# wall_power.net
KiCad netlist of a schematic drawn in EAGLE
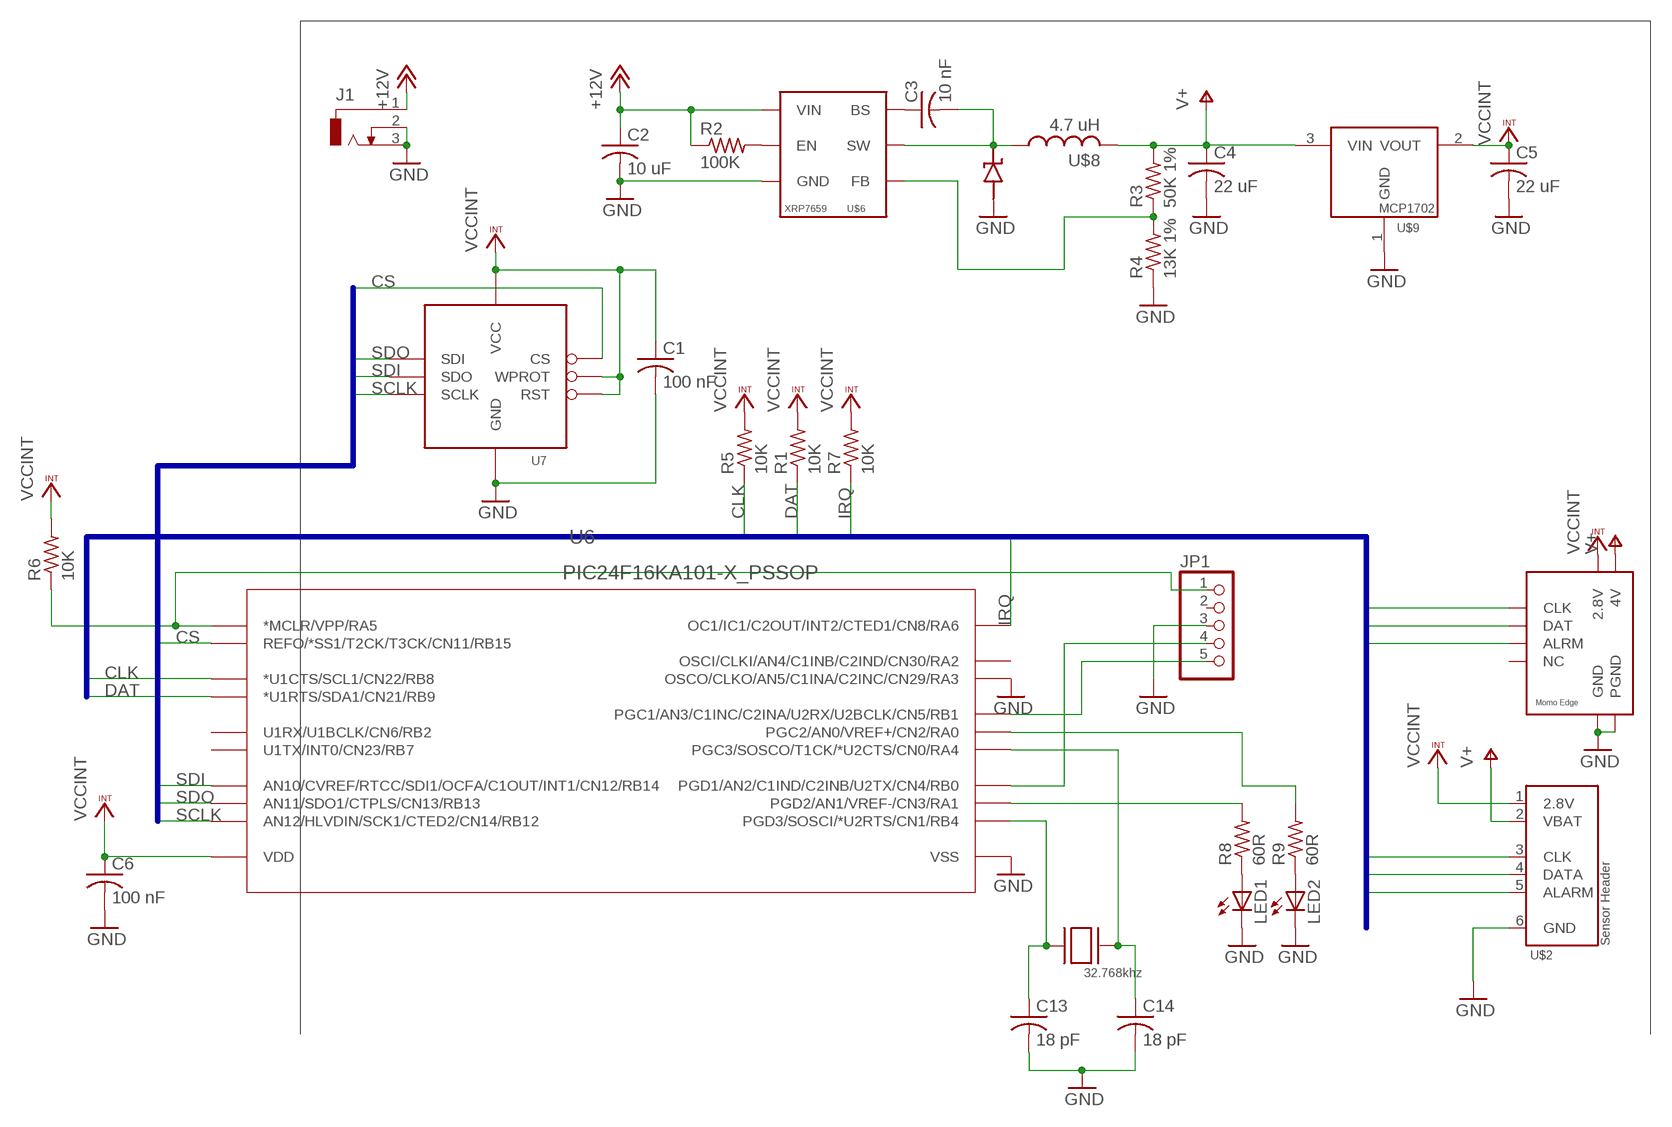
[diagram p0: schematic, sheet 1]

(export (version "E")
  (design (tool "Eeschema 10.0.6"))
  (components
    (comp (ref "C1")
      (value "100 nF")
      (footprint "eagle-import:C0402")
      (libsource (lib "eagle-import") (part "C-USC0402"))
    )
    (comp (ref "C2")
      (value "10 uF")
      (footprint "eagle-import:C0805")
      (libsource (lib "eagle-import") (part "C-USC0805"))
    )
    (comp (ref "C3")
      (value "10 nF")
      (footprint "eagle-import:C0402")
      (libsource (lib "eagle-import") (part "C-USC0402"))
    )
    (comp (ref "C4")
      (value "22 uF")
      (footprint "eagle-import:C1206")
      (libsource (lib "eagle-import") (part "C-USC1206"))
    )
    (comp (ref "C5")
      (value "22 uF")
      (footprint "eagle-import:C0402")
      (libsource (lib "eagle-import") (part "C-USC0402"))
    )
    (comp (ref "C6")
      (value "100 nF")
      (footprint "eagle-import:C0402")
      (libsource (lib "eagle-import") (part "C-USC0402"))
    )
    (comp (ref "C13")
      (value "18 pF")
      (footprint "eagle-import:C0402K")
      (libsource (lib "eagle-import") (part "C-USC0402K"))
    )
    (comp (ref "C14")
      (value "18 pF")
      (footprint "eagle-import:C0402K")
      (libsource (lib "eagle-import") (part "C-USC0402K"))
    )
    (comp (ref "J1")
      (value "DCJ0303")
      (footprint "eagle-import:DCJ0303")
      (libsource (lib "eagle-import") (part "DCJ0303"))
    )
    (comp (ref "JP1")
      (value "PINHD-1X5")
      (footprint "eagle-import:1X05")
      (libsource (lib "eagle-import") (part "PINHD-1X5"))
    )
    (comp (ref "LED1")
      (value "LEDSML0603")
      (footprint "eagle-import:SML0603")
      (libsource (lib "eagle-import") (part "LEDSML0603"))
    )
    (comp (ref "LED2")
      (value "LEDSML0603")
      (footprint "eagle-import:SML0603")
      (libsource (lib "eagle-import") (part "LEDSML0603"))
    )
    (comp (ref "R1")
      (value "10K")
      (footprint "eagle-import:R0603")
      (libsource (lib "eagle-import") (part "R-US_R0603"))
    )
    (comp (ref "R2")
      (value "100K")
      (footprint "eagle-import:R0603")
      (libsource (lib "eagle-import") (part "R-US_R0603"))
    )
    (comp (ref "R3")
      (value "50K 1%")
      (footprint "eagle-import:R0603")
      (libsource (lib "eagle-import") (part "R-US_R0603"))
    )
    (comp (ref "R4")
      (value "13K 1%")
      (footprint "eagle-import:R0603")
      (libsource (lib "eagle-import") (part "R-US_R0603"))
    )
    (comp (ref "R5")
      (value "10K")
      (footprint "eagle-import:R0603")
      (libsource (lib "eagle-import") (part "R-US_R0603"))
    )
    (comp (ref "R6")
      (value "10K")
      (footprint "eagle-import:R0603")
      (libsource (lib "eagle-import") (part "R-US_R0603"))
    )
    (comp (ref "R7")
      (value "10K")
      (footprint "eagle-import:R0603")
      (libsource (lib "eagle-import") (part "R-US_R0603"))
    )
    (comp (ref "R8")
      (value "60R")
      (footprint "eagle-import:R0603")
      (libsource (lib "eagle-import") (part "R-US_R0603"))
    )
    (comp (ref "R9")
      (value "60R")
      (footprint "eagle-import:R0603")
      (libsource (lib "eagle-import") (part "R-US_R0603"))
    )
    (comp (ref "U$1")
      (value "MOMO-EDGE-8F")
      (footprint "eagle-import:MOMO-EDGE-8F")
      (libsource (lib "eagle-import") (part "MOMO-EDGE-8F"))
    )
    (comp (ref "U$2")
      (value "MOMO-SENSOR-HEADER")
      (footprint "eagle-import:2X3-MOLEX-90130@1")
      (libsource (lib "eagle-import") (part "MOMO-SENSOR-HEADER"))
    )
    (comp (ref "U$6")
      (value "XRP7659")
      (footprint "eagle-import:SOT23-6L")
      (libsource (lib "eagle-import") (part "XRP7659"))
    )
    (comp (ref "U$7")
      (value "DIODE_SS2P3")
      (footprint "eagle-import:DIODE_SS2P3")
      (libsource (lib "eagle-import") (part "DIODE_SS2P3"))
    )
    (comp (ref "U$8")
      (value "4.7 uH")
      (footprint "eagle-import:NR6028-INDUCTOR")
      (libsource (lib "eagle-import") (part "NR6028-INDUCTOR"))
    )
    (comp (ref "U$9")
      (value "MCP1702")
      (footprint "eagle-import:SOT23")
      (libsource (lib "eagle-import") (part "MCP1702"))
    )
    (comp (ref "U6")
      (value "PIC24F16KA101-X_PSSOP")
      (footprint "eagle-import:SSOP20")
      (libsource (lib "eagle-import") (part "PIC24F16KA101-X_PSSOP"))
    )
    (comp (ref "U7")
      (value "FLASH8MSOP8")
      (footprint "eagle-import:SOP08")
      (libsource (lib "eagle-import") (part "FLASH8MSOP8"))
    )
    (comp (ref "XTAL1")
      (value "32.768khz")
      (footprint "eagle-import:1206")
      (libsource (lib "eagle-import") (part "SMD-XTAL"))
    )
  )
  (nets
    (net (code "1") (name "+12V") (class "Default")
      (node (ref "C2") (pin "1") (pinfunction "1_1") (pintype "passive"))
      (node (ref "J1") (pin "1") (pinfunction "1_1") (pintype "passive"))
      (node (ref "R2") (pin "1") (pinfunction "1_1") (pintype "passive"))
      (node (ref "U$6") (pin "5") (pinfunction "VIN_5") (pintype "bidirectional"))
    )
    (net (code "2") (name "/CLK") (class "Default")
      (node (ref "R5") (pin "1") (pinfunction "1_1") (pintype "passive"))
      (node (ref "U$1") (pin "CLK") (pinfunction "CLK_CLK") (pintype "bidirectional"))
      (node (ref "U$2") (pin "3") (pinfunction "CLK_3") (pintype "bidirectional"))
      (node (ref "U6") (pin "12") (pinfunction "*U1CTS/SCL1/CN22/RB8_12") (pintype "bidirectional"))
    )
    (net (code "3") (name "/CS") (class "Default")
      (node (ref "U6") (pin "18") (pinfunction "REFO/*SS1/T2CK/T3CK/CN11/RB15_18") (pintype "bidirectional"))
      (node (ref "U7") (pin "1") (pinfunction "CS_1") (pintype "bidirectional"))
    )
    (net (code "4") (name "/DAT") (class "Default")
      (node (ref "R1") (pin "1") (pinfunction "1_1") (pintype "passive"))
      (node (ref "U$1") (pin "DAT") (pinfunction "DAT_DAT") (pintype "bidirectional"))
      (node (ref "U$2") (pin "4") (pinfunction "DATA_4") (pintype "bidirectional"))
      (node (ref "U6") (pin "13") (pinfunction "*U1RTS/SDA1/CN21/RB9_13") (pintype "bidirectional"))
    )
    (net (code "5") (name "/IRQ") (class "Default")
      (node (ref "R7") (pin "1") (pinfunction "1_1") (pintype "passive"))
      (node (ref "U$1") (pin "ARLM") (pinfunction "ALRM_ARLM") (pintype "bidirectional"))
      (node (ref "U$2") (pin "5") (pinfunction "ALARM_5") (pintype "bidirectional"))
      (node (ref "U6") (pin "14") (pinfunction "OC1/IC1/C2OUT/INT2/CTED1/CN8/RA6_14") (pintype "bidirectional"))
    )
    (net (code "6") (name "/SCLK") (class "Default")
      (node (ref "U6") (pin "15") (pinfunction "AN12/HLVDIN/SCK1/CTED2/CN14/RB12_15") (pintype "bidirectional"))
      (node (ref "U7") (pin "6") (pinfunction "SCLK_6") (pintype "bidirectional"))
    )
    (net (code "7") (name "/SDI") (class "Default")
      (node (ref "U6") (pin "17") (pinfunction "AN10/CVREF/RTCC/SDI1/OCFA/C1OUT/INT1/CN12/RB14_17") (pintype "bidirectional"))
      (node (ref "U7") (pin "2") (pinfunction "SDO_2") (pintype "bidirectional"))
    )
    (net (code "8") (name "/SDO") (class "Default")
      (node (ref "U6") (pin "16") (pinfunction "AN11/SDO1/CTPLS/CN13/RB13_16") (pintype "bidirectional"))
      (node (ref "U7") (pin "5") (pinfunction "SDI_5") (pintype "bidirectional"))
    )
    (net (code "9") (name "GND") (class "Default")
      (node (ref "C1") (pin "2") (pinfunction "2_2") (pintype "passive"))
      (node (ref "C13") (pin "2") (pinfunction "2_2") (pintype "passive"))
      (node (ref "C14") (pin "2") (pinfunction "2_2") (pintype "passive"))
      (node (ref "C2") (pin "2") (pinfunction "2_2") (pintype "passive"))
      (node (ref "C4") (pin "2") (pinfunction "2_2") (pintype "passive"))
      (node (ref "C5") (pin "2") (pinfunction "2_2") (pintype "passive"))
      (node (ref "C6") (pin "2") (pinfunction "2_2") (pintype "passive"))
      (node (ref "J1") (pin "2") (pinfunction "2_2") (pintype "passive"))
      (node (ref "J1") (pin "3") (pinfunction "3_3") (pintype "passive"))
      (node (ref "JP1") (pin "3") (pinfunction "3_3") (pintype "passive"))
      (node (ref "LED1") (pin "C") (pinfunction "C_C") (pintype "passive"))
      (node (ref "LED2") (pin "C") (pinfunction "C_C") (pintype "passive"))
      (node (ref "R4") (pin "1") (pinfunction "1_1") (pintype "passive"))
      (node (ref "U$1") (pin "GND") (pinfunction "GND_GND") (pintype "power_in"))
      (node (ref "U$1") (pin "PGND") (pinfunction "PGND_PGND") (pintype "power_in"))
      (node (ref "U$2") (pin "6") (pinfunction "GND_6") (pintype "bidirectional"))
      (node (ref "U$6") (pin "2") (pinfunction "GND_2") (pintype "bidirectional"))
      (node (ref "U$7") (pin "AN") (pinfunction "AN_AN") (pintype "bidirectional"))
      (node (ref "U$9") (pin "1") (pinfunction "GND_1") (pintype "bidirectional"))
      (node (ref "U6") (pin "19") (pinfunction "VSS_19") (pintype "power_in"))
      (node (ref "U6") (pin "8") (pinfunction "OSCO/CLKO/AN5/C1INA/C2INC/CN29/RA3_8") (pintype "bidirectional"))
      (node (ref "U7") (pin "4") (pinfunction "GND_4") (pintype "power_in"))
    )
    (net (code "10") (name "Net-(LED1-PadA)") (class "Default")
      (node (ref "LED1") (pin "A") (pinfunction "A_A") (pintype "passive"))
      (node (ref "R8") (pin "1") (pinfunction "1_1") (pintype "passive"))
    )
    (net (code "11") (name "Net-(LED2-PadA)") (class "Default")
      (node (ref "LED2") (pin "A") (pinfunction "A_A") (pintype "passive"))
      (node (ref "R9") (pin "1") (pinfunction "1_1") (pintype "passive"))
    )
    (net (code "12") (name "Net-(U$6-BS)") (class "Default")
      (node (ref "C3") (pin "1") (pinfunction "1_1") (pintype "passive"))
      (node (ref "U$6") (pin "1") (pinfunction "BS_1") (pintype "bidirectional"))
    )
    (net (code "13") (name "Net-(U$6-EN)") (class "Default")
      (node (ref "R2") (pin "2") (pinfunction "2_2") (pintype "passive"))
      (node (ref "U$6") (pin "4") (pinfunction "EN_4") (pintype "bidirectional"))
    )
    (net (code "14") (name "Net-(U$6-FB)") (class "Default")
      (node (ref "R3") (pin "1") (pinfunction "1_1") (pintype "passive"))
      (node (ref "R4") (pin "2") (pinfunction "2_2") (pintype "passive"))
      (node (ref "U$6") (pin "3") (pinfunction "FB_3") (pintype "bidirectional"))
    )
    (net (code "15") (name "Net-(U$6-SW)") (class "Default")
      (node (ref "C3") (pin "2") (pinfunction "2_2") (pintype "passive"))
      (node (ref "U$6") (pin "6") (pinfunction "SW_6") (pintype "bidirectional"))
      (node (ref "U$7") (pin "CATH") (pinfunction "CATH_CATH") (pintype "bidirectional"))
      (node (ref "U$8") (pin "1") (pinfunction "1_1") (pintype "passive"))
    )
    (net (code "16") (name "Net-(U6-*MCLR{slash}VPP{slash}RA5)") (class "Default")
      (node (ref "JP1") (pin "1") (pinfunction "1_1") (pintype "passive"))
      (node (ref "R6") (pin "1") (pinfunction "1_1") (pintype "passive"))
      (node (ref "U6") (pin "1") (pinfunction "*MCLR/VPP/RA5_1") (pintype "bidirectional"))
    )
    (net (code "17") (name "Net-(U6-PGC1{slash}AN3{slash}C1INC{slash}C2INA{slash}U2RX{slash}U2BCLK{slash}CN5{slash}RB1)") (class "Default")
      (node (ref "JP1") (pin "5") (pinfunction "5_5") (pintype "passive"))
      (node (ref "U6") (pin "5") (pinfunction "PGC1/AN3/C1INC/C2INA/U2RX/U2BCLK/CN5/RB1_5") (pintype "bidirectional"))
    )
    (net (code "18") (name "Net-(U6-PGC2{slash}AN0{slash}VREF+{slash}CN2{slash}RA0)") (class "Default")
      (node (ref "R9") (pin "2") (pinfunction "2_2") (pintype "passive"))
      (node (ref "U6") (pin "2") (pinfunction "PGC2/AN0/VREF+/CN2/RA0_2") (pintype "bidirectional"))
    )
    (net (code "19") (name "Net-(U6-PGC3{slash}SOSCO{slash}T1CK{slash}*U2CTS{slash}CN0{slash}RA4)") (class "Default")
      (node (ref "C14") (pin "1") (pinfunction "1_1") (pintype "passive"))
      (node (ref "U6") (pin "10") (pinfunction "PGC3/SOSCO/T1CK/*U2CTS/CN0/RA4_10") (pintype "bidirectional"))
      (node (ref "XTAL1") (pin "P$2") (pinfunction "XTAL2_P$2") (pintype "bidirectional"))
    )
    (net (code "20") (name "Net-(U6-PGD1{slash}AN2{slash}C1IND{slash}C2INB{slash}U2TX{slash}CN4{slash}RB0)") (class "Default")
      (node (ref "JP1") (pin "4") (pinfunction "4_4") (pintype "passive"))
      (node (ref "U6") (pin "4") (pinfunction "PGD1/AN2/C1IND/C2INB/U2TX/CN4/RB0_4") (pintype "bidirectional"))
    )
    (net (code "21") (name "Net-(U6-PGD2{slash}AN1{slash}VREF-{slash}CN3{slash}RA1)") (class "Default")
      (node (ref "R8") (pin "2") (pinfunction "2_2") (pintype "passive"))
      (node (ref "U6") (pin "3") (pinfunction "PGD2/AN1/VREF-/CN3/RA1_3") (pintype "bidirectional"))
    )
    (net (code "22") (name "Net-(U6-PGD3{slash}SOSCI{slash}*U2RTS{slash}CN1{slash}RB4)") (class "Default")
      (node (ref "C13") (pin "1") (pinfunction "1_1") (pintype "passive"))
      (node (ref "U6") (pin "9") (pinfunction "PGD3/SOSCI/*U2RTS/CN1/RB4_9") (pintype "bidirectional"))
      (node (ref "XTAL1") (pin "P$1") (pinfunction "XTAL1_P$1") (pintype "bidirectional"))
    )
    (net (code "23") (name "V+") (class "Default")
      (node (ref "C4") (pin "1") (pinfunction "1_1") (pintype "passive"))
      (node (ref "R3") (pin "2") (pinfunction "2_2") (pintype "passive"))
      (node (ref "U$1") (pin "V4.") (pinfunction "4V_V4.") (pintype "power_in"))
      (node (ref "U$2") (pin "2") (pinfunction "VBAT_2") (pintype "bidirectional"))
      (node (ref "U$8") (pin "2") (pinfunction "2_2") (pintype "passive"))
      (node (ref "U$9") (pin "3") (pinfunction "VIN_3") (pintype "bidirectional"))
    )
    (net (code "24") (name "VCCINT") (class "Default")
      (node (ref "C1") (pin "1") (pinfunction "1_1") (pintype "passive"))
      (node (ref "C5") (pin "1") (pinfunction "1_1") (pintype "passive"))
      (node (ref "C6") (pin "1") (pinfunction "1_1") (pintype "passive"))
      (node (ref "R1") (pin "2") (pinfunction "2_2") (pintype "passive"))
      (node (ref "R5") (pin "2") (pinfunction "2_2") (pintype "passive"))
      (node (ref "R6") (pin "2") (pinfunction "2_2") (pintype "passive"))
      (node (ref "R7") (pin "2") (pinfunction "2_2") (pintype "passive"))
      (node (ref "U$1") (pin "V28") (pinfunction "2.8V_V28") (pintype "power_in"))
      (node (ref "U$2") (pin "1") (pinfunction "2.8V_1") (pintype "bidirectional"))
      (node (ref "U$9") (pin "2") (pinfunction "VOUT_2") (pintype "bidirectional"))
      (node (ref "U6") (pin "20") (pinfunction "VDD_20") (pintype "power_in"))
      (node (ref "U7") (pin "3") (pinfunction "WPROT_3") (pintype "bidirectional"))
      (node (ref "U7") (pin "7") (pinfunction "RST_7") (pintype "bidirectional"))
      (node (ref "U7") (pin "8") (pinfunction "VCC_8") (pintype "power_in"))
    )
    (net (code "25") (name "unconnected-(JP1-Pad2)") (class "Default")
      (node (ref "JP1") (pin "2") (pinfunction "2_2") (pintype "passive"))
    )
    (net (code "26") (name "unconnected-(U$1-NC-PadNV)") (class "Default")
      (node (ref "U$1") (pin "NV") (pinfunction "NC_NV") (pintype "bidirectional"))
    )
    (net (code "27") (name "unconnected-(U6-OSCI{slash}CLKI{slash}AN4{slash}C1INB{slash}C2IND{slash}CN30{slash}RA2-Pad7)") (class "Default")
      (node (ref "U6") (pin "7") (pinfunction "OSCI/CLKI/AN4/C1INB/C2IND/CN30/RA2_7") (pintype "bidirectional"))
    )
    (net (code "28") (name "unconnected-(U6-U1RX{slash}U1BCLK{slash}CN6{slash}RB2-Pad6)") (class "Default")
      (node (ref "U6") (pin "6") (pinfunction "U1RX/U1BCLK/CN6/RB2_6") (pintype "bidirectional"))
    )
    (net (code "29") (name "unconnected-(U6-U1TX{slash}INT0{slash}CN23{slash}RB7-Pad11)") (class "Default")
      (node (ref "U6") (pin "11") (pinfunction "U1TX/INT0/CN23/RB7_11") (pintype "bidirectional"))
    )
  )
)
